# Proto_V1.net
KiCad netlist of a schematic drawn in EAGLE
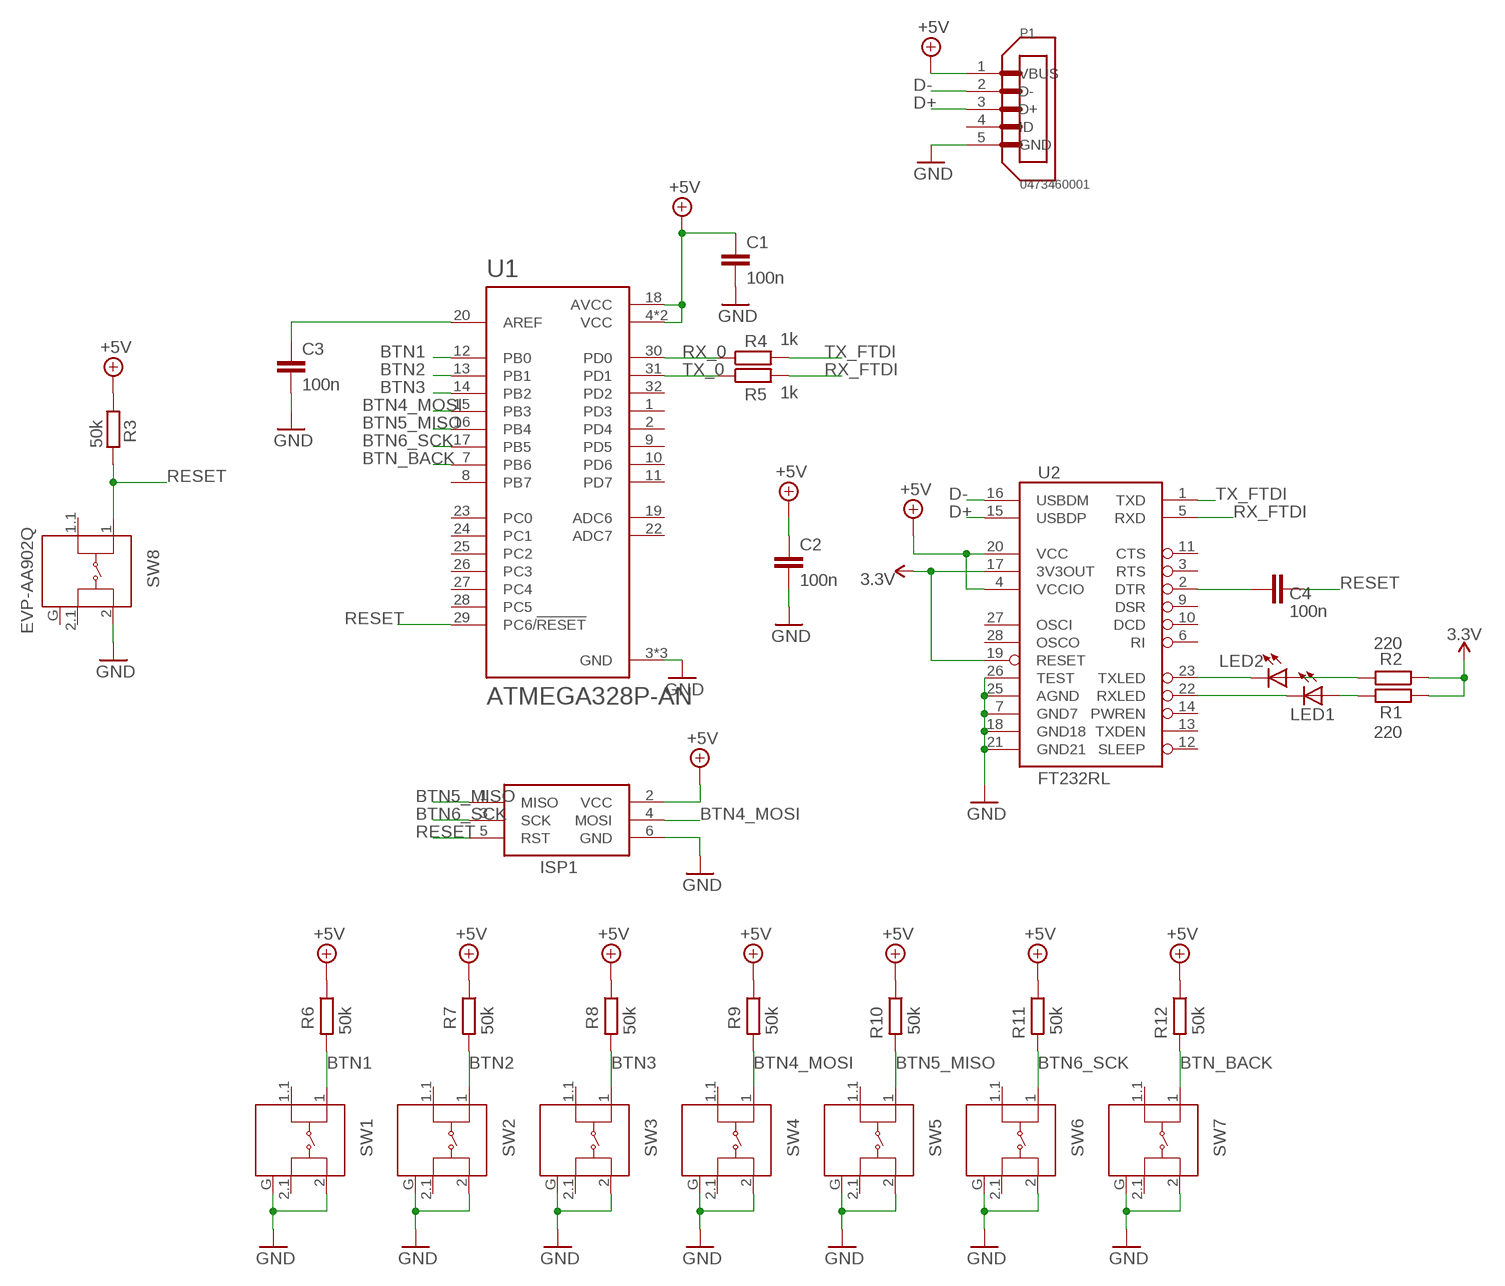
[diagram p0: schematic, sheet 1]

(export (version "E")
  (design (tool "Eeschema 10.0.6"))
  (components
    (comp (ref "C1")
      (value "100n")
      (footprint "eagle-import:CAP_0805")
      (fields
        (field (name "DIGIKEY_PART_NUMBER") "311-1140-2-ND")
        (field (name "MANUFACTURER") "Yageo")
        (field (name "MPN") "CC0805KRX7R9BB104")
        (field (name "CREATED_BY") "PCBLayout.com")
      )
      (libsource (lib "eagle-import") (part "CC0805KRX7R9BB104"))
    )
    (comp (ref "C2")
      (value "100n")
      (footprint "eagle-import:CAP_0805")
      (fields
        (field (name "DIGIKEY_PART_NUMBER") "311-1140-2-ND")
        (field (name "MANUFACTURER") "Yageo")
        (field (name "MPN") "CC0805KRX7R9BB104")
        (field (name "CREATED_BY") "PCBLayout.com")
      )
      (libsource (lib "eagle-import") (part "CC0805KRX7R9BB104"))
    )
    (comp (ref "C3")
      (value "100n")
      (footprint "eagle-import:CAP_0805")
      (fields
        (field (name "DIGIKEY_PART_NUMBER") "311-1140-2-ND")
        (field (name "MANUFACTURER") "Yageo")
        (field (name "MPN") "CC0805KRX7R9BB104")
        (field (name "CREATED_BY") "PCBLayout.com")
      )
      (libsource (lib "eagle-import") (part "CC0805KRX7R9BB104"))
    )
    (comp (ref "C4")
      (value "100n")
      (footprint "eagle-import:CAP_0805")
      (fields
        (field (name "DIGIKEY_PART_NUMBER") "311-1140-2-ND")
        (field (name "MANUFACTURER") "Yageo")
        (field (name "MPN") "CC0805KRX7R9BB104")
        (field (name "CREATED_BY") "PCBLayout.com")
      )
      (libsource (lib "eagle-import") (part "CC0805KRX7R9BB104"))
    )
    (comp (ref "ISP1")
      (value "AVRISP-6")
      (footprint "eagle-import:AVRISP")
      (libsource (lib "eagle-import") (part "AVRISP-6"))
    )
    (comp (ref "LED1")
      (value "LEDCHIP-LED0805")
      (footprint "eagle-import:CHIP-LED0805")
      (libsource (lib "eagle-import") (part "LEDCHIP-LED0805"))
    )
    (comp (ref "LED2")
      (value "LEDCHIP-LED0805")
      (footprint "eagle-import:CHIP-LED0805")
      (libsource (lib "eagle-import") (part "LEDCHIP-LED0805"))
    )
    (comp (ref "P1")
      (value "0473460001")
      (footprint "eagle-import:MOLEX_0473460001")
      (fields (field (name "MF") "Weidmuller"))
      (libsource (lib "eagle-import") (part "0473460001"))
    )
    (comp (ref "R1")
      (value "220")
      (footprint "eagle-import:R0805")
      (libsource (lib "eagle-import") (part "R-EU_R0805"))
    )
    (comp (ref "R2")
      (value "220")
      (footprint "eagle-import:R0805")
      (libsource (lib "eagle-import") (part "R-EU_R0805"))
    )
    (comp (ref "R3")
      (value "50k")
      (footprint "eagle-import:R0805")
      (libsource (lib "eagle-import") (part "R-EU_R0805"))
    )
    (comp (ref "R4")
      (value "1k")
      (footprint "eagle-import:R0805")
      (libsource (lib "eagle-import") (part "R-EU_R0805"))
    )
    (comp (ref "R5")
      (value "1k")
      (footprint "eagle-import:R0805")
      (libsource (lib "eagle-import") (part "R-EU_R0805"))
    )
    (comp (ref "R6")
      (value "50k")
      (footprint "eagle-import:R0805")
      (libsource (lib "eagle-import") (part "R-EU_R0805"))
    )
    (comp (ref "R7")
      (value "50k")
      (footprint "eagle-import:R0805")
      (libsource (lib "eagle-import") (part "R-EU_R0805"))
    )
    (comp (ref "R8")
      (value "50k")
      (footprint "eagle-import:R0805")
      (libsource (lib "eagle-import") (part "R-EU_R0805"))
    )
    (comp (ref "R9")
      (value "50k")
      (footprint "eagle-import:R0805")
      (libsource (lib "eagle-import") (part "R-EU_R0805"))
    )
    (comp (ref "R10")
      (value "50k")
      (footprint "eagle-import:R0805")
      (libsource (lib "eagle-import") (part "R-EU_R0805"))
    )
    (comp (ref "R11")
      (value "50k")
      (footprint "eagle-import:R0805")
      (libsource (lib "eagle-import") (part "R-EU_R0805"))
    )
    (comp (ref "R12")
      (value "50k")
      (footprint "eagle-import:R0805")
      (libsource (lib "eagle-import") (part "R-EU_R0805"))
    )
    (comp (ref "SW1")
      (value "EVP-AA902Q")
      (footprint "eagle-import:EVP-AA902Q")
      (fields
        (field (name "DIGIKEY_PARTNO") "P15193TR-ND")
        (field (name "MANUFACTURER") "Panasonic Electronic Components")
        (field (name "CREATED_BY") "PCBLayout.com")
      )
      (libsource (lib "eagle-import") (part "EVP-AA902Q"))
    )
    (comp (ref "SW2")
      (value "EVP-AA902Q")
      (footprint "eagle-import:EVP-AA902Q")
      (fields
        (field (name "DIGIKEY_PARTNO") "P15193TR-ND")
        (field (name "MANUFACTURER") "Panasonic Electronic Components")
        (field (name "CREATED_BY") "PCBLayout.com")
      )
      (libsource (lib "eagle-import") (part "EVP-AA902Q"))
    )
    (comp (ref "SW3")
      (value "EVP-AA902Q")
      (footprint "eagle-import:EVP-AA902Q")
      (fields
        (field (name "DIGIKEY_PARTNO") "P15193TR-ND")
        (field (name "MANUFACTURER") "Panasonic Electronic Components")
        (field (name "CREATED_BY") "PCBLayout.com")
      )
      (libsource (lib "eagle-import") (part "EVP-AA902Q"))
    )
    (comp (ref "SW4")
      (value "EVP-AA902Q")
      (footprint "eagle-import:EVP-AA902Q")
      (fields
        (field (name "DIGIKEY_PARTNO") "P15193TR-ND")
        (field (name "MANUFACTURER") "Panasonic Electronic Components")
        (field (name "CREATED_BY") "PCBLayout.com")
      )
      (libsource (lib "eagle-import") (part "EVP-AA902Q"))
    )
    (comp (ref "SW5")
      (value "EVP-AA902Q")
      (footprint "eagle-import:EVP-AA902Q")
      (fields
        (field (name "DIGIKEY_PARTNO") "P15193TR-ND")
        (field (name "MANUFACTURER") "Panasonic Electronic Components")
        (field (name "CREATED_BY") "PCBLayout.com")
      )
      (libsource (lib "eagle-import") (part "EVP-AA902Q"))
    )
    (comp (ref "SW6")
      (value "EVP-AA902Q")
      (footprint "eagle-import:EVP-AA902Q")
      (fields
        (field (name "DIGIKEY_PARTNO") "P15193TR-ND")
        (field (name "MANUFACTURER") "Panasonic Electronic Components")
        (field (name "CREATED_BY") "PCBLayout.com")
      )
      (libsource (lib "eagle-import") (part "EVP-AA902Q"))
    )
    (comp (ref "SW7")
      (value "EVP-AA902Q")
      (footprint "eagle-import:EVP-AA902Q")
      (fields
        (field (name "DIGIKEY_PARTNO") "P15193TR-ND")
        (field (name "MANUFACTURER") "Panasonic Electronic Components")
        (field (name "CREATED_BY") "PCBLayout.com")
      )
      (libsource (lib "eagle-import") (part "EVP-AA902Q"))
    )
    (comp (ref "SW8")
      (value "EVP-AA902Q")
      (footprint "eagle-import:EVP-AA902Q")
      (fields
        (field (name "DIGIKEY_PARTNO") "P15193TR-ND")
        (field (name "MANUFACTURER") "Panasonic Electronic Components")
        (field (name "CREATED_BY") "PCBLayout.com")
      )
      (libsource (lib "eagle-import") (part "EVP-AA902Q"))
    )
    (comp (ref "U1")
      (value "ATMEGA328P-AN")
      (footprint "eagle-import:QFP80P900X900X120-32N")
      (fields (field (name "MF") "Microchip"))
      (libsource (lib "eagle-import") (part "ATMEGA328P-AN"))
    )
    (comp (ref "U2")
      (value "FT232RL")
      (footprint "eagle-import:SSOP28DB")
      (libsource (lib "eagle-import") (part "FT232RLSSOP"))
    )
  )
  (nets
    (net (code "1") (name "+5V") (class "Default")
      (node (ref "C1") (pin "1") (pinfunction "1_1") (pintype "passive"))
      (node (ref "C2") (pin "1") (pinfunction "1_1") (pintype "passive"))
      (node (ref "ISP1") (pin "2") (pinfunction "VCC_2") (pintype "power_in"))
      (node (ref "P1") (pin "1") (pinfunction "VBUS_1") (pintype "power_in"))
      (node (ref "R10") (pin "1") (pinfunction "1_1") (pintype "passive"))
      (node (ref "R11") (pin "1") (pinfunction "1_1") (pintype "passive"))
      (node (ref "R12") (pin "1") (pinfunction "1_1") (pintype "passive"))
      (node (ref "R3") (pin "1") (pinfunction "1_1") (pintype "passive"))
      (node (ref "R6") (pin "1") (pinfunction "1_1") (pintype "passive"))
      (node (ref "R7") (pin "1") (pinfunction "1_1") (pintype "passive"))
      (node (ref "R8") (pin "1") (pinfunction "1_1") (pintype "passive"))
      (node (ref "R9") (pin "1") (pinfunction "1_1") (pintype "passive"))
      (node (ref "U1") (pin "18") (pinfunction "AVCC_18") (pintype "power_in"))
      (node (ref "U1") (pin "4") (pinfunction "VCC_4") (pintype "power_in"))
      (node (ref "U1") (pin "6") (pinfunction "VCC_6") (pintype "power_in"))
      (node (ref "U2") (pin "20") (pinfunction "VCC_20") (pintype "power_in"))
      (node (ref "U2") (pin "4") (pinfunction "VCCIO_4") (pintype "power_in"))
    )
    (net (code "2") (name "/BTN1") (class "Default")
      (node (ref "R6") (pin "2") (pinfunction "2_2") (pintype "passive"))
      (node (ref "SW1") (pin "1") (pinfunction "1_1") (pintype "passive"))
      (node (ref "U1") (pin "12") (pinfunction "PB0_12") (pintype "bidirectional"))
    )
    (net (code "3") (name "/BTN2") (class "Default")
      (node (ref "R7") (pin "2") (pinfunction "2_2") (pintype "passive"))
      (node (ref "SW2") (pin "1") (pinfunction "1_1") (pintype "passive"))
      (node (ref "U1") (pin "13") (pinfunction "PB1_13") (pintype "bidirectional"))
    )
    (net (code "4") (name "/BTN3") (class "Default")
      (node (ref "R8") (pin "2") (pinfunction "2_2") (pintype "passive"))
      (node (ref "SW3") (pin "1") (pinfunction "1_1") (pintype "passive"))
      (node (ref "U1") (pin "14") (pinfunction "PB2_14") (pintype "bidirectional"))
    )
    (net (code "5") (name "/BTN4_MOSI") (class "Default")
      (node (ref "ISP1") (pin "4") (pinfunction "MOSI_4") (pintype "output"))
      (node (ref "R9") (pin "2") (pinfunction "2_2") (pintype "passive"))
      (node (ref "SW4") (pin "1") (pinfunction "1_1") (pintype "passive"))
      (node (ref "U1") (pin "15") (pinfunction "PB3_15") (pintype "bidirectional"))
    )
    (net (code "6") (name "/BTN5_MISO") (class "Default")
      (node (ref "ISP1") (pin "1") (pinfunction "MISO_1") (pintype "input"))
      (node (ref "R10") (pin "2") (pinfunction "2_2") (pintype "passive"))
      (node (ref "SW5") (pin "1") (pinfunction "1_1") (pintype "passive"))
      (node (ref "U1") (pin "16") (pinfunction "PB4_16") (pintype "bidirectional"))
    )
    (net (code "7") (name "/BTN6_SCK") (class "Default")
      (node (ref "ISP1") (pin "3") (pinfunction "SCK_3") (pintype "output"))
      (node (ref "R11") (pin "2") (pinfunction "2_2") (pintype "passive"))
      (node (ref "SW6") (pin "1") (pinfunction "1_1") (pintype "passive"))
      (node (ref "U1") (pin "17") (pinfunction "PB5_17") (pintype "bidirectional"))
    )
    (net (code "8") (name "/BTN_BACK") (class "Default")
      (node (ref "R12") (pin "2") (pinfunction "2_2") (pintype "passive"))
      (node (ref "SW7") (pin "1") (pinfunction "1_1") (pintype "passive"))
      (node (ref "U1") (pin "7") (pinfunction "PB6_7") (pintype "bidirectional"))
    )
    (net (code "9") (name "/D+") (class "Default")
      (node (ref "P1") (pin "3") (pinfunction "D+_3") (pintype "bidirectional"))
      (node (ref "U2") (pin "15") (pinfunction "USBDP_15") (pintype "bidirectional"))
    )
    (net (code "10") (name "/D-") (class "Default")
      (node (ref "P1") (pin "2") (pinfunction "D-_2") (pintype "bidirectional"))
      (node (ref "U2") (pin "16") (pinfunction "USBDM_16") (pintype "bidirectional"))
    )
    (net (code "11") (name "/RESET") (class "Default")
      (node (ref "C4") (pin "1") (pinfunction "1_1") (pintype "passive"))
      (node (ref "ISP1") (pin "5") (pinfunction "RST_5") (pintype "output"))
      (node (ref "R3") (pin "2") (pinfunction "2_2") (pintype "passive"))
      (node (ref "SW8") (pin "1") (pinfunction "1_1") (pintype "passive"))
      (node (ref "U1") (pin "29") (pinfunction "PC6/~{RESET}_29") (pintype "bidirectional"))
    )
    (net (code "12") (name "/RX_0") (class "Default")
      (node (ref "R4") (pin "1") (pinfunction "1_1") (pintype "passive"))
      (node (ref "U1") (pin "30") (pinfunction "PD0_30") (pintype "bidirectional"))
    )
    (net (code "13") (name "/RX_FTDI") (class "Default")
      (node (ref "R5") (pin "2") (pinfunction "2_2") (pintype "passive"))
      (node (ref "U2") (pin "5") (pinfunction "RXD_5") (pintype "input"))
    )
    (net (code "14") (name "/TX_0") (class "Default")
      (node (ref "R5") (pin "1") (pinfunction "1_1") (pintype "passive"))
      (node (ref "U1") (pin "31") (pinfunction "PD1_31") (pintype "bidirectional"))
    )
    (net (code "15") (name "/TX_FTDI") (class "Default")
      (node (ref "R4") (pin "2") (pinfunction "2_2") (pintype "passive"))
      (node (ref "U2") (pin "1") (pinfunction "TXD_1") (pintype "output"))
    )
    (net (code "16") (name "3.3V") (class "Default")
      (node (ref "R1") (pin "1") (pinfunction "1_1") (pintype "passive"))
      (node (ref "R2") (pin "1") (pinfunction "1_1") (pintype "passive"))
      (node (ref "U2") (pin "17") (pinfunction "3V3OUT_17") (pintype "output"))
      (node (ref "U2") (pin "19") (pinfunction "RESET_19") (pintype "input"))
    )
    (net (code "17") (name "GND") (class "Default")
      (node (ref "C1") (pin "2") (pinfunction "2_2") (pintype "passive"))
      (node (ref "C2") (pin "2") (pinfunction "2_2") (pintype "passive"))
      (node (ref "C3") (pin "2") (pinfunction "2_2") (pintype "passive"))
      (node (ref "ISP1") (pin "6") (pinfunction "GND_6") (pintype "power_in"))
      (node (ref "P1") (pin "5") (pinfunction "GND_5") (pintype "passive"))
      (node (ref "SW1") (pin "2") (pinfunction "2_2") (pintype "passive"))
      (node (ref "SW1") (pin "G") (pinfunction "SHIELD_G") (pintype "passive"))
      (node (ref "SW2") (pin "2") (pinfunction "2_2") (pintype "passive"))
      (node (ref "SW2") (pin "G") (pinfunction "SHIELD_G") (pintype "passive"))
      (node (ref "SW3") (pin "2") (pinfunction "2_2") (pintype "passive"))
      (node (ref "SW3") (pin "G") (pinfunction "SHIELD_G") (pintype "passive"))
      (node (ref "SW4") (pin "2") (pinfunction "2_2") (pintype "passive"))
      (node (ref "SW4") (pin "G") (pinfunction "SHIELD_G") (pintype "passive"))
      (node (ref "SW5") (pin "2") (pinfunction "2_2") (pintype "passive"))
      (node (ref "SW5") (pin "G") (pinfunction "SHIELD_G") (pintype "passive"))
      (node (ref "SW6") (pin "2") (pinfunction "2_2") (pintype "passive"))
      (node (ref "SW6") (pin "G") (pinfunction "SHIELD_G") (pintype "passive"))
      (node (ref "SW7") (pin "2") (pinfunction "2_2") (pintype "passive"))
      (node (ref "SW7") (pin "G") (pinfunction "SHIELD_G") (pintype "passive"))
      (node (ref "SW8") (pin "2") (pinfunction "2_2") (pintype "passive"))
      (node (ref "U1") (pin "21") (pinfunction "GND_21") (pintype "power_in"))
      (node (ref "U1") (pin "3") (pinfunction "GND_3") (pintype "power_in"))
      (node (ref "U1") (pin "5") (pinfunction "GND_5") (pintype "power_in"))
      (node (ref "U2") (pin "18") (pinfunction "GND18_18") (pintype "power_in"))
      (node (ref "U2") (pin "21") (pinfunction "GND21_21") (pintype "power_in"))
      (node (ref "U2") (pin "25") (pinfunction "AGND_25") (pintype "power_in"))
      (node (ref "U2") (pin "26") (pinfunction "TEST_26") (pintype "input"))
      (node (ref "U2") (pin "7") (pinfunction "GND7_7") (pintype "power_in"))
    )
    (net (code "18") (name "Net-(LED1-PadA)") (class "Default")
      (node (ref "LED1") (pin "A") (pinfunction "A_A") (pintype "passive"))
      (node (ref "R1") (pin "2") (pinfunction "2_2") (pintype "passive"))
    )
    (net (code "19") (name "Net-(LED2-PadA)") (class "Default")
      (node (ref "LED2") (pin "A") (pinfunction "A_A") (pintype "passive"))
      (node (ref "R2") (pin "2") (pinfunction "2_2") (pintype "passive"))
    )
    (net (code "20") (name "Net-(U1-AREF)") (class "Default")
      (node (ref "C3") (pin "1") (pinfunction "1_1") (pintype "passive"))
      (node (ref "U1") (pin "20") (pinfunction "AREF_20") (pintype "input"))
    )
    (net (code "21") (name "Net-(U2-DTR)") (class "Default")
      (node (ref "C4") (pin "2") (pinfunction "2_2") (pintype "passive"))
      (node (ref "U2") (pin "2") (pinfunction "DTR_2") (pintype "output"))
    )
    (net (code "22") (name "Net-(U2-RXLED)") (class "Default")
      (node (ref "LED1") (pin "C") (pinfunction "C_C") (pintype "passive"))
      (node (ref "U2") (pin "22") (pinfunction "RXLED_22") (pintype "input"))
    )
    (net (code "23") (name "Net-(U2-TXLED)") (class "Default")
      (node (ref "LED2") (pin "C") (pinfunction "C_C") (pintype "passive"))
      (node (ref "U2") (pin "23") (pinfunction "TXLED_23") (pintype "input"))
    )
    (net (code "24") (name "unconnected-(P1-ID-Pad4)") (class "Default")
      (node (ref "P1") (pin "4") (pinfunction "ID_4") (pintype "bidirectional"))
    )
    (net (code "25") (name "unconnected-(SW1-Pad1.1)") (class "Default")
      (node (ref "SW1") (pin "1.1") (pinfunction "1.1_1.1") (pintype "passive"))
    )
    (net (code "26") (name "unconnected-(SW1-Pad2.1)") (class "Default")
      (node (ref "SW1") (pin "2.1") (pinfunction "2.1_2.1") (pintype "passive"))
    )
    (net (code "27") (name "unconnected-(SW2-Pad1.1)") (class "Default")
      (node (ref "SW2") (pin "1.1") (pinfunction "1.1_1.1") (pintype "passive"))
    )
    (net (code "28") (name "unconnected-(SW2-Pad2.1)") (class "Default")
      (node (ref "SW2") (pin "2.1") (pinfunction "2.1_2.1") (pintype "passive"))
    )
    (net (code "29") (name "unconnected-(SW3-Pad1.1)") (class "Default")
      (node (ref "SW3") (pin "1.1") (pinfunction "1.1_1.1") (pintype "passive"))
    )
    (net (code "30") (name "unconnected-(SW3-Pad2.1)") (class "Default")
      (node (ref "SW3") (pin "2.1") (pinfunction "2.1_2.1") (pintype "passive"))
    )
    (net (code "31") (name "unconnected-(SW4-Pad1.1)") (class "Default")
      (node (ref "SW4") (pin "1.1") (pinfunction "1.1_1.1") (pintype "passive"))
    )
    (net (code "32") (name "unconnected-(SW4-Pad2.1)") (class "Default")
      (node (ref "SW4") (pin "2.1") (pinfunction "2.1_2.1") (pintype "passive"))
    )
    (net (code "33") (name "unconnected-(SW5-Pad1.1)") (class "Default")
      (node (ref "SW5") (pin "1.1") (pinfunction "1.1_1.1") (pintype "passive"))
    )
    (net (code "34") (name "unconnected-(SW5-Pad2.1)") (class "Default")
      (node (ref "SW5") (pin "2.1") (pinfunction "2.1_2.1") (pintype "passive"))
    )
    (net (code "35") (name "unconnected-(SW6-Pad1.1)") (class "Default")
      (node (ref "SW6") (pin "1.1") (pinfunction "1.1_1.1") (pintype "passive"))
    )
    (net (code "36") (name "unconnected-(SW6-Pad2.1)") (class "Default")
      (node (ref "SW6") (pin "2.1") (pinfunction "2.1_2.1") (pintype "passive"))
    )
    (net (code "37") (name "unconnected-(SW7-Pad1.1)") (class "Default")
      (node (ref "SW7") (pin "1.1") (pinfunction "1.1_1.1") (pintype "passive"))
    )
    (net (code "38") (name "unconnected-(SW7-Pad2.1)") (class "Default")
      (node (ref "SW7") (pin "2.1") (pinfunction "2.1_2.1") (pintype "passive"))
    )
    (net (code "39") (name "unconnected-(SW8-Pad1.1)") (class "Default")
      (node (ref "SW8") (pin "1.1") (pinfunction "1.1_1.1") (pintype "passive"))
    )
    (net (code "40") (name "unconnected-(SW8-Pad2.1)") (class "Default")
      (node (ref "SW8") (pin "2.1") (pinfunction "2.1_2.1") (pintype "passive"))
    )
    (net (code "41") (name "unconnected-(SW8-SHIELD-PadG)") (class "Default")
      (node (ref "SW8") (pin "G") (pinfunction "SHIELD_G") (pintype "passive"))
    )
    (net (code "42") (name "unconnected-(U1-ADC6-Pad19)") (class "Default")
      (node (ref "U1") (pin "19") (pinfunction "ADC6_19") (pintype "bidirectional"))
    )
    (net (code "43") (name "unconnected-(U1-ADC7-Pad22)") (class "Default")
      (node (ref "U1") (pin "22") (pinfunction "ADC7_22") (pintype "bidirectional"))
    )
    (net (code "44") (name "unconnected-(U1-PB7-Pad8)") (class "Default")
      (node (ref "U1") (pin "8") (pinfunction "PB7_8") (pintype "bidirectional"))
    )
    (net (code "45") (name "unconnected-(U1-PC0-Pad23)") (class "Default")
      (node (ref "U1") (pin "23") (pinfunction "PC0_23") (pintype "bidirectional"))
    )
    (net (code "46") (name "unconnected-(U1-PC1-Pad24)") (class "Default")
      (node (ref "U1") (pin "24") (pinfunction "PC1_24") (pintype "bidirectional"))
    )
    (net (code "47") (name "unconnected-(U1-PC2-Pad25)") (class "Default")
      (node (ref "U1") (pin "25") (pinfunction "PC2_25") (pintype "bidirectional"))
    )
    (net (code "48") (name "unconnected-(U1-PC3-Pad26)") (class "Default")
      (node (ref "U1") (pin "26") (pinfunction "PC3_26") (pintype "bidirectional"))
    )
    (net (code "49") (name "unconnected-(U1-PC4-Pad27)") (class "Default")
      (node (ref "U1") (pin "27") (pinfunction "PC4_27") (pintype "bidirectional"))
    )
    (net (code "50") (name "unconnected-(U1-PC5-Pad28)") (class "Default")
      (node (ref "U1") (pin "28") (pinfunction "PC5_28") (pintype "bidirectional"))
    )
    (net (code "51") (name "unconnected-(U1-PD2-Pad32)") (class "Default")
      (node (ref "U1") (pin "32") (pinfunction "PD2_32") (pintype "bidirectional"))
    )
    (net (code "52") (name "unconnected-(U1-PD3-Pad1)") (class "Default")
      (node (ref "U1") (pin "1") (pinfunction "PD3_1") (pintype "bidirectional"))
    )
    (net (code "53") (name "unconnected-(U1-PD4-Pad2)") (class "Default")
      (node (ref "U1") (pin "2") (pinfunction "PD4_2") (pintype "bidirectional"))
    )
    (net (code "54") (name "unconnected-(U1-PD5-Pad9)") (class "Default")
      (node (ref "U1") (pin "9") (pinfunction "PD5_9") (pintype "bidirectional"))
    )
    (net (code "55") (name "unconnected-(U1-PD6-Pad10)") (class "Default")
      (node (ref "U1") (pin "10") (pinfunction "PD6_10") (pintype "bidirectional"))
    )
    (net (code "56") (name "unconnected-(U1-PD7-Pad11)") (class "Default")
      (node (ref "U1") (pin "11") (pinfunction "PD7_11") (pintype "bidirectional"))
    )
    (net (code "57") (name "unconnected-(U2-CTS-Pad11)") (class "Default")
      (node (ref "U2") (pin "11") (pinfunction "CTS_11") (pintype "input"))
    )
    (net (code "58") (name "unconnected-(U2-DCD-Pad10)") (class "Default")
      (node (ref "U2") (pin "10") (pinfunction "DCD_10") (pintype "input"))
    )
    (net (code "59") (name "unconnected-(U2-DSR-Pad9)") (class "Default")
      (node (ref "U2") (pin "9") (pinfunction "DSR_9") (pintype "input"))
    )
    (net (code "60") (name "unconnected-(U2-OSCI-Pad27)") (class "Default")
      (node (ref "U2") (pin "27") (pinfunction "OSCI_27") (pintype "input"))
    )
    (net (code "61") (name "unconnected-(U2-OSCO-Pad28)") (class "Default")
      (node (ref "U2") (pin "28") (pinfunction "OSCO_28") (pintype "output"))
    )
    (net (code "62") (name "unconnected-(U2-PWREN-Pad14)") (class "Default")
      (node (ref "U2") (pin "14") (pinfunction "PWREN_14") (pintype "input"))
    )
    (net (code "63") (name "unconnected-(U2-RI-Pad6)") (class "Default")
      (node (ref "U2") (pin "6") (pinfunction "RI_6") (pintype "input"))
    )
    (net (code "64") (name "unconnected-(U2-RTS-Pad3)") (class "Default")
      (node (ref "U2") (pin "3") (pinfunction "RTS_3") (pintype "output"))
    )
    (net (code "65") (name "unconnected-(U2-SLEEP-Pad12)") (class "Default")
      (node (ref "U2") (pin "12") (pinfunction "SLEEP_12") (pintype "input"))
    )
    (net (code "66") (name "unconnected-(U2-TXDEN-Pad13)") (class "Default")
      (node (ref "U2") (pin "13") (pinfunction "TXDEN_13") (pintype "input"))
    )
  )
)
